# FT232-Breakout.net
KiCad netlist of a schematic drawn in EAGLE
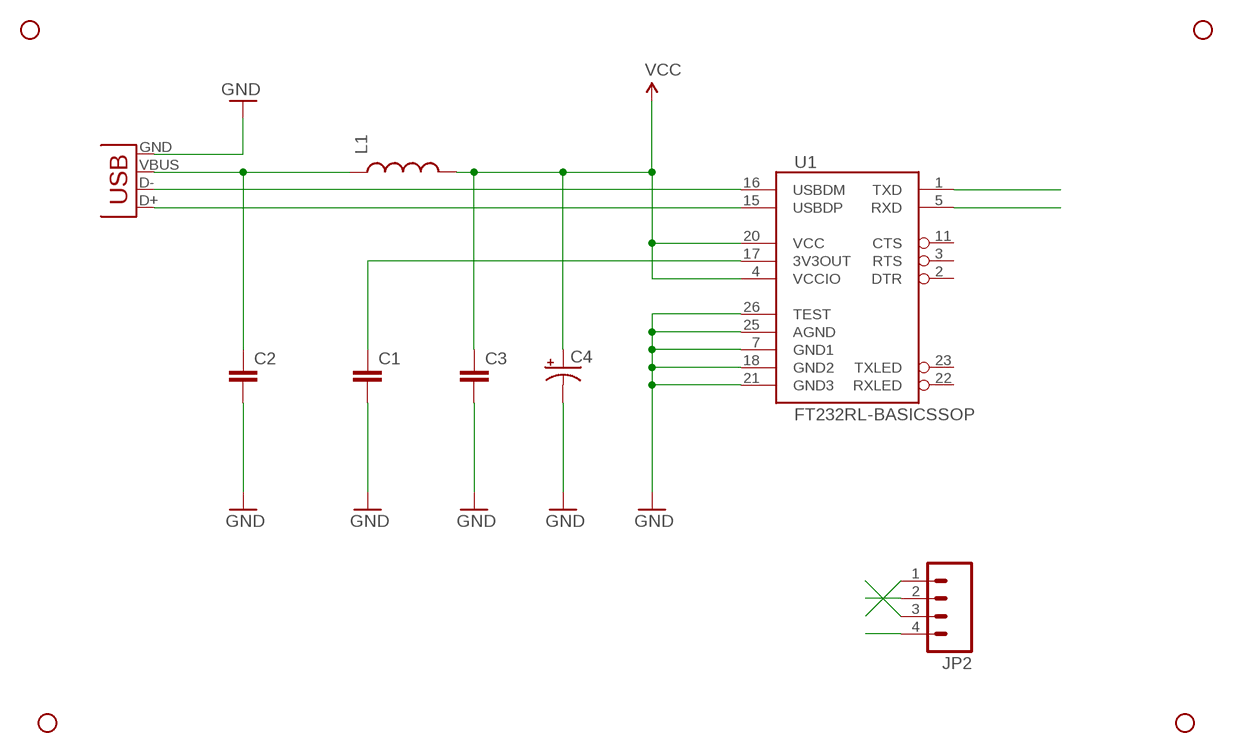
[diagram p0: schematic, sheet 1]

(export (version "E")
  (design (tool "Eeschema 10.0.6"))
  (components
    (comp (ref "C1")
      (value "CAP0603-CAP")
      (footprint "eagle-import:0603-CAP")
      (libsource (lib "eagle-import") (part "CAP0603-CAP"))
    )
    (comp (ref "C2")
      (value "CAP0603-CAP")
      (footprint "eagle-import:0603-CAP")
      (libsource (lib "eagle-import") (part "CAP0603-CAP"))
    )
    (comp (ref "C3")
      (value "CAP0603-CAP")
      (footprint "eagle-import:0603-CAP")
      (libsource (lib "eagle-import") (part "CAP0603-CAP"))
    )
    (comp (ref "C4")
      (value "CAP_POL1206")
      (footprint "eagle-import:EIA3216")
      (libsource (lib "eagle-import") (part "CAP_POL1206"))
    )
    (comp (ref "JP1")
      (value "USB-B")
      (footprint "eagle-import:USB-B-PTH")
      (libsource (lib "eagle-import") (part "USBPTH"))
    )
    (comp (ref "JP2")
      (value "M04PTH")
      (footprint "eagle-import:1X04")
      (libsource (lib "eagle-import") (part "M04PTH"))
    )
    (comp (ref "L1")
      (value "INDUCTOR0603")
      (footprint "eagle-import:0603")
      (libsource (lib "eagle-import") (part "INDUCTOR0603"))
    )
    (comp (ref "STANDOFF1")
      (value "STAND-OFF")
      (footprint "eagle-import:STAND-OFF")
      (libsource (lib "eagle-import") (part "STAND-OFF"))
    )
    (comp (ref "STANDOFF2")
      (value "STAND-OFF")
      (footprint "eagle-import:STAND-OFF")
      (libsource (lib "eagle-import") (part "STAND-OFF"))
    )
    (comp (ref "STANDOFF3")
      (value "STAND-OFF")
      (footprint "eagle-import:STAND-OFF")
      (libsource (lib "eagle-import") (part "STAND-OFF"))
    )
    (comp (ref "STANDOFF4")
      (value "STAND-OFF")
      (footprint "eagle-import:STAND-OFF")
      (libsource (lib "eagle-import") (part "STAND-OFF"))
    )
    (comp (ref "U1")
      (value "FT232RL-BASICSSOP")
      (footprint "eagle-import:SSOP28DB")
      (libsource (lib "eagle-import") (part "FT232RL-BASICSSOP"))
    )
  )
  (nets
    (net (code "1") (name "/RX") (class "Default")
      (node (ref "JP2") (pin "2") (pinfunction "2_2") (pintype "passive"))
      (node (ref "U1") (pin "5") (pinfunction "RXD_5") (pintype "input"))
    )
    (net (code "2") (name "/TX") (class "Default")
      (node (ref "JP2") (pin "3") (pinfunction "3_3") (pintype "passive"))
      (node (ref "U1") (pin "1") (pinfunction "TXD_1") (pintype "output"))
    )
    (net (code "3") (name "GND") (class "Default")
      (node (ref "C1") (pin "2") (pinfunction "2_2") (pintype "passive"))
      (node (ref "C2") (pin "2") (pinfunction "2_2") (pintype "passive"))
      (node (ref "C3") (pin "2") (pinfunction "2_2") (pintype "passive"))
      (node (ref "C4") (pin "C") (pinfunction "-_C") (pintype "passive"))
      (node (ref "JP1") (pin "GND") (pinfunction "GND_GND") (pintype "bidirectional"))
      (node (ref "JP2") (pin "1") (pinfunction "1_1") (pintype "passive"))
      (node (ref "U1") (pin "18") (pinfunction "GND2_18") (pintype "power_in"))
      (node (ref "U1") (pin "21") (pinfunction "GND3_21") (pintype "power_in"))
      (node (ref "U1") (pin "25") (pinfunction "AGND_25") (pintype "power_in"))
      (node (ref "U1") (pin "26") (pinfunction "TEST_26") (pintype "input"))
      (node (ref "U1") (pin "7") (pinfunction "GND1_7") (pintype "power_in"))
    )
    (net (code "4") (name "Net-(C2-Pad1)") (class "Default")
      (node (ref "C2") (pin "1") (pinfunction "1_1") (pintype "passive"))
      (node (ref "JP1") (pin "VBUS") (pinfunction "VBUS_VBUS") (pintype "bidirectional"))
      (node (ref "L1") (pin "1") (pinfunction "1_1") (pintype "passive"))
    )
    (net (code "5") (name "Net-(U1-3V3OUT)") (class "Default")
      (node (ref "C1") (pin "1") (pinfunction "1_1") (pintype "passive"))
      (node (ref "U1") (pin "17") (pinfunction "3V3OUT_17") (pintype "output"))
    )
    (net (code "6") (name "Net-(U1-USBDM)") (class "Default")
      (node (ref "JP1") (pin "D-") (pinfunction "D-_D-") (pintype "bidirectional"))
      (node (ref "U1") (pin "16") (pinfunction "USBDM_16") (pintype "bidirectional"))
    )
    (net (code "7") (name "Net-(U1-USBDP)") (class "Default")
      (node (ref "JP1") (pin "D+") (pinfunction "D+_D+") (pintype "bidirectional"))
      (node (ref "U1") (pin "15") (pinfunction "USBDP_15") (pintype "bidirectional"))
    )
    (net (code "8") (name "VCC") (class "Default")
      (node (ref "C3") (pin "1") (pinfunction "1_1") (pintype "passive"))
      (node (ref "C4") (pin "A") (pinfunction "+_A") (pintype "passive"))
      (node (ref "JP2") (pin "4") (pinfunction "4_4") (pintype "passive"))
      (node (ref "L1") (pin "2") (pinfunction "2_2") (pintype "passive"))
      (node (ref "U1") (pin "20") (pinfunction "VCC_20") (pintype "power_in"))
      (node (ref "U1") (pin "4") (pinfunction "VCCIO_4") (pintype "power_in"))
    )
    (net (code "9") (name "unconnected-(U1-CTS-Pad11)") (class "Default")
      (node (ref "U1") (pin "11") (pinfunction "CTS_11") (pintype "bidirectional"))
    )
    (net (code "10") (name "unconnected-(U1-DTR-Pad2)") (class "Default")
      (node (ref "U1") (pin "2") (pinfunction "DTR_2") (pintype "bidirectional"))
    )
    (net (code "11") (name "unconnected-(U1-RTS-Pad3)") (class "Default")
      (node (ref "U1") (pin "3") (pinfunction "RTS_3") (pintype "bidirectional"))
    )
    (net (code "12") (name "unconnected-(U1-RXLED-Pad22)") (class "Default")
      (node (ref "U1") (pin "22") (pinfunction "RXLED_22") (pintype "bidirectional"))
    )
    (net (code "13") (name "unconnected-(U1-TXLED-Pad23)") (class "Default")
      (node (ref "U1") (pin "23") (pinfunction "TXLED_23") (pintype "bidirectional"))
    )
  )
)
